# regsimple2addfp_copy.net
KiCad netlist of a schematic drawn in EAGLE
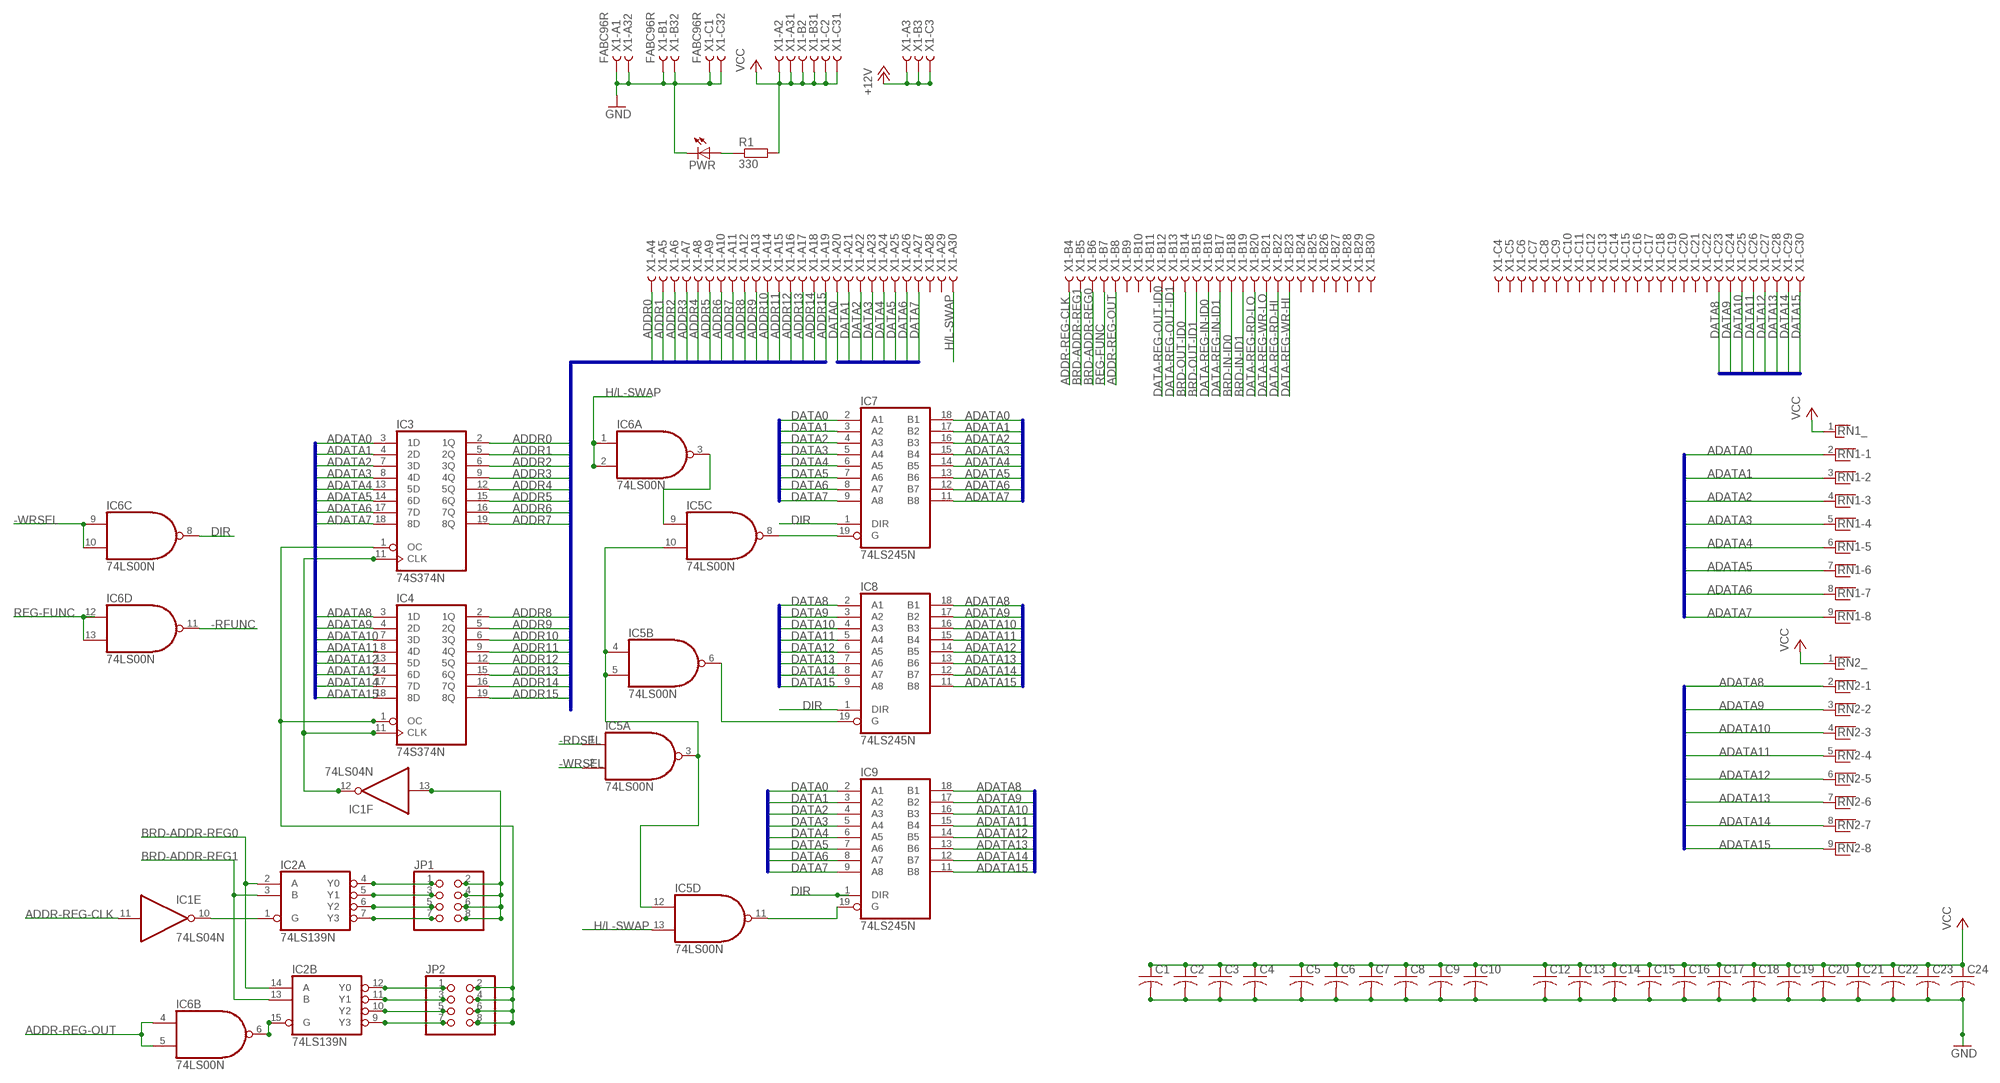
[diagram p0: schematic, sheet 1]
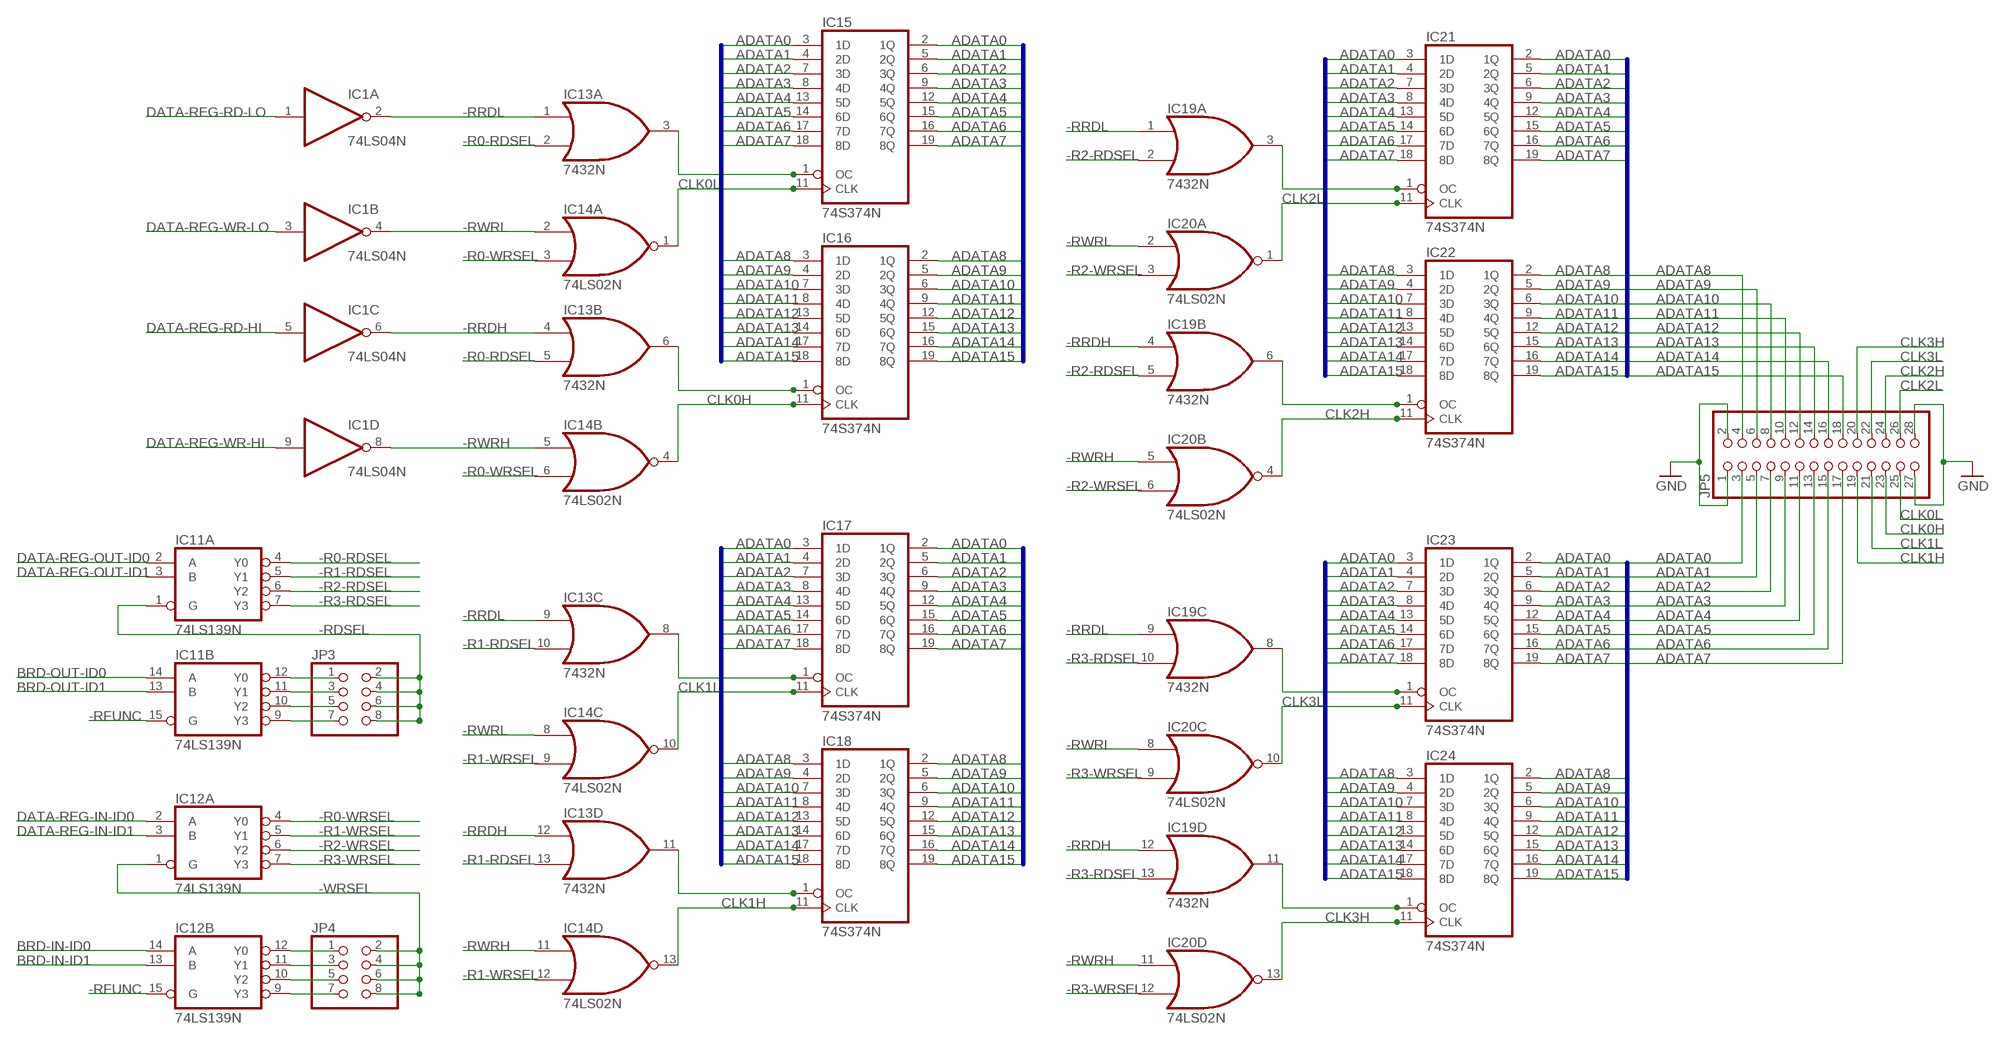
[diagram p1: schematic, sheet 2]

(export (version "E")
  (design (tool "Eeschema 10.0.6"))
  (components
    (comp (ref "C1")
      (value "C-US025-040X050")
      (footprint "eagle-import:C025-040X050")
      (libsource (lib "eagle-import") (part "C-US025-040X050"))
    )
    (comp (ref "C2")
      (value "C-US025-040X050")
      (footprint "eagle-import:C025-040X050")
      (libsource (lib "eagle-import") (part "C-US025-040X050"))
    )
    (comp (ref "C3")
      (value "C-US025-040X050")
      (footprint "eagle-import:C025-040X050")
      (libsource (lib "eagle-import") (part "C-US025-040X050"))
    )
    (comp (ref "C4")
      (value "C-US025-040X050")
      (footprint "eagle-import:C025-040X050")
      (libsource (lib "eagle-import") (part "C-US025-040X050"))
    )
    (comp (ref "C5")
      (value "C-US025-040X050")
      (footprint "eagle-import:C025-040X050")
      (libsource (lib "eagle-import") (part "C-US025-040X050"))
    )
    (comp (ref "C6")
      (value "C-US025-040X050")
      (footprint "eagle-import:C025-040X050")
      (libsource (lib "eagle-import") (part "C-US025-040X050"))
    )
    (comp (ref "C7")
      (value "C-US025-040X050")
      (footprint "eagle-import:C025-040X050")
      (libsource (lib "eagle-import") (part "C-US025-040X050"))
    )
    (comp (ref "C8")
      (value "C-US025-040X050")
      (footprint "eagle-import:C025-040X050")
      (libsource (lib "eagle-import") (part "C-US025-040X050"))
    )
    (comp (ref "C9")
      (value "C-US025-040X050")
      (footprint "eagle-import:C025-040X050")
      (libsource (lib "eagle-import") (part "C-US025-040X050"))
    )
    (comp (ref "C10")
      (value "C-US025-040X050")
      (footprint "eagle-import:C025-040X050")
      (libsource (lib "eagle-import") (part "C-US025-040X050"))
    )
    (comp (ref "C12")
      (value "C-US025-040X050")
      (footprint "eagle-import:C025-040X050")
      (libsource (lib "eagle-import") (part "C-US025-040X050"))
    )
    (comp (ref "C13")
      (value "C-US025-040X050")
      (footprint "eagle-import:C025-040X050")
      (libsource (lib "eagle-import") (part "C-US025-040X050"))
    )
    (comp (ref "C14")
      (value "C-US025-040X050")
      (footprint "eagle-import:C025-040X050")
      (libsource (lib "eagle-import") (part "C-US025-040X050"))
    )
    (comp (ref "C15")
      (value "C-US025-040X050")
      (footprint "eagle-import:C025-040X050")
      (libsource (lib "eagle-import") (part "C-US025-040X050"))
    )
    (comp (ref "C16")
      (value "C-US025-040X050")
      (footprint "eagle-import:C025-040X050")
      (libsource (lib "eagle-import") (part "C-US025-040X050"))
    )
    (comp (ref "C17")
      (value "C-US025-040X050")
      (footprint "eagle-import:C025-040X050")
      (libsource (lib "eagle-import") (part "C-US025-040X050"))
    )
    (comp (ref "C18")
      (value "C-US025-040X050")
      (footprint "eagle-import:C025-040X050")
      (libsource (lib "eagle-import") (part "C-US025-040X050"))
    )
    (comp (ref "C19")
      (value "C-US025-040X050")
      (footprint "eagle-import:C025-040X050")
      (libsource (lib "eagle-import") (part "C-US025-040X050"))
    )
    (comp (ref "C20")
      (value "C-US025-040X050")
      (footprint "eagle-import:C025-040X050")
      (libsource (lib "eagle-import") (part "C-US025-040X050"))
    )
    (comp (ref "C21")
      (value "C-US025-040X050")
      (footprint "eagle-import:C025-040X050")
      (libsource (lib "eagle-import") (part "C-US025-040X050"))
    )
    (comp (ref "C22")
      (value "C-US025-040X050")
      (footprint "eagle-import:C025-040X050")
      (libsource (lib "eagle-import") (part "C-US025-040X050"))
    )
    (comp (ref "C23")
      (value "C-US025-040X050")
      (footprint "eagle-import:C025-040X050")
      (libsource (lib "eagle-import") (part "C-US025-040X050"))
    )
    (comp (ref "C24")
      (value "C-US025-040X050")
      (footprint "eagle-import:C025-040X050")
      (libsource (lib "eagle-import") (part "C-US025-040X050"))
    )
    (comp (ref "IC1")
      (value "74LS04N")
      (footprint "eagle-import:DIL14")
      (libsource (lib "eagle-import") (part "7404NLS"))
    )
    (comp (ref "IC2")
      (value "74LS139N")
      (footprint "eagle-import:DIL16")
      (libsource (lib "eagle-import") (part "74139NLS"))
    )
    (comp (ref "IC3")
      (value "74S374N")
      (footprint "eagle-import:DIL20")
      (libsource (lib "eagle-import") (part "74374NS"))
    )
    (comp (ref "IC4")
      (value "74S374N")
      (footprint "eagle-import:DIL20")
      (libsource (lib "eagle-import") (part "74374NS"))
    )
    (comp (ref "IC5")
      (value "74LS00N")
      (footprint "eagle-import:DIL14")
      (libsource (lib "eagle-import") (part "7400NLS"))
    )
    (comp (ref "IC6")
      (value "74LS00N")
      (footprint "eagle-import:DIL14")
      (libsource (lib "eagle-import") (part "7400NLS"))
    )
    (comp (ref "IC7")
      (value "74LS245N")
      (footprint "eagle-import:DIL20")
      (libsource (lib "eagle-import") (part "74245NLS"))
    )
    (comp (ref "IC8")
      (value "74LS245N")
      (footprint "eagle-import:DIL20")
      (libsource (lib "eagle-import") (part "74245NLS"))
    )
    (comp (ref "IC9")
      (value "74LS245N")
      (footprint "eagle-import:DIL20")
      (libsource (lib "eagle-import") (part "74245NLS"))
    )
    (comp (ref "JP1")
      (value "PINHD-2X4")
      (footprint "eagle-import:2X04")
      (libsource (lib "eagle-import") (part "PINHD-2X4"))
    )
    (comp (ref "JP2")
      (value "PINHD-2X4")
      (footprint "eagle-import:2X04")
      (libsource (lib "eagle-import") (part "PINHD-2X4"))
    )
    (comp (ref "PWR")
      (value "LED5MM")
      (footprint "eagle-import:LED5MM")
      (libsource (lib "eagle-import") (part "LED5MM"))
    )
    (comp (ref "R1")
      (value "330")
      (footprint "eagle-import:0207_10")
      (libsource (lib "eagle-import") (part "R0207/10"))
    )
    (comp (ref "RN1")
      (value "RNX8")
      (footprint "eagle-import:RN-9")
      (libsource (lib "eagle-import") (part "RNX8"))
    )
    (comp (ref "RN2")
      (value "RNX8")
      (footprint "eagle-import:RN-9")
      (libsource (lib "eagle-import") (part "RNX8"))
    )
    (comp (ref "X1")
      (value "FABC96R")
      (footprint "eagle-import:FABC96R")
      (libsource (lib "eagle-import") (part "FABC96R"))
    )
    (comp (ref "IC11")
      (value "74LS139N")
      (footprint "eagle-import:DIL16")
      (libsource (lib "eagle-import") (part "74139NLS"))
    )
    (comp (ref "IC12")
      (value "74LS139N")
      (footprint "eagle-import:DIL16")
      (libsource (lib "eagle-import") (part "74139NLS"))
    )
    (comp (ref "IC13")
      (value "7432N")
      (footprint "eagle-import:DIL14")
      (libsource (lib "eagle-import") (part "7432N"))
    )
    (comp (ref "IC14")
      (value "74LS02N")
      (footprint "eagle-import:DIL14")
      (libsource (lib "eagle-import") (part "7402NLS"))
    )
    (comp (ref "IC15")
      (value "74S374N")
      (footprint "eagle-import:DIL20")
      (libsource (lib "eagle-import") (part "74374NS"))
    )
    (comp (ref "IC16")
      (value "74S374N")
      (footprint "eagle-import:DIL20")
      (libsource (lib "eagle-import") (part "74374NS"))
    )
    (comp (ref "IC17")
      (value "74S374N")
      (footprint "eagle-import:DIL20")
      (libsource (lib "eagle-import") (part "74374NS"))
    )
    (comp (ref "IC18")
      (value "74S374N")
      (footprint "eagle-import:DIL20")
      (libsource (lib "eagle-import") (part "74374NS"))
    )
    (comp (ref "IC19")
      (value "7432N")
      (footprint "eagle-import:DIL14")
      (libsource (lib "eagle-import") (part "7432N"))
    )
    (comp (ref "IC20")
      (value "74LS02N")
      (footprint "eagle-import:DIL14")
      (libsource (lib "eagle-import") (part "7402NLS"))
    )
    (comp (ref "IC21")
      (value "74S374N")
      (footprint "eagle-import:DIL20")
      (libsource (lib "eagle-import") (part "74374NS"))
    )
    (comp (ref "IC22")
      (value "74S374N")
      (footprint "eagle-import:DIL20")
      (libsource (lib "eagle-import") (part "74374NS"))
    )
    (comp (ref "IC23")
      (value "74S374N")
      (footprint "eagle-import:DIL20")
      (libsource (lib "eagle-import") (part "74374NS"))
    )
    (comp (ref "IC24")
      (value "74S374N")
      (footprint "eagle-import:DIL20")
      (libsource (lib "eagle-import") (part "74374NS"))
    )
    (comp (ref "JP3")
      (value "PINHD-2X4")
      (footprint "eagle-import:2X04")
      (libsource (lib "eagle-import") (part "PINHD-2X4"))
    )
    (comp (ref "JP4")
      (value "PINHD-2X4")
      (footprint "eagle-import:2X04")
      (libsource (lib "eagle-import") (part "PINHD-2X4"))
    )
    (comp (ref "JP5")
      (value "PINHD-2X14")
      (footprint "eagle-import:2X14")
      (libsource (lib "eagle-import") (part "PINHD-2X14"))
    )
  )
  (nets
    (net (code "1") (name "+12V") (class "Default")
      (node (ref "X1") (pin "A3") (pinfunction "B_A3") (pintype "passive"))
      (node (ref "X1") (pin "B3") (pinfunction "B_B3") (pintype "passive"))
      (node (ref "X1") (pin "C3") (pinfunction "B_C3") (pintype "passive"))
    )
    (net (code "2") (name "-R0-RDSEL") (class "Default")
      (node (ref "IC11") (pin "4") (pinfunction "Y0_4") (pintype "output"))
      (node (ref "IC13") (pin "2") (pinfunction "I1_2") (pintype "input"))
      (node (ref "IC13") (pin "5") (pinfunction "I1_5") (pintype "input"))
    )
    (net (code "3") (name "-R0-WRSEL") (class "Default")
      (node (ref "IC12") (pin "4") (pinfunction "Y0_4") (pintype "output"))
      (node (ref "IC14") (pin "3") (pinfunction "I1_3") (pintype "input"))
      (node (ref "IC14") (pin "6") (pinfunction "I1_6") (pintype "input"))
    )
    (net (code "4") (name "-R1-RDSEL") (class "Default")
      (node (ref "IC11") (pin "5") (pinfunction "Y1_5") (pintype "output"))
      (node (ref "IC13") (pin "10") (pinfunction "I1_10") (pintype "input"))
      (node (ref "IC13") (pin "13") (pinfunction "I1_13") (pintype "input"))
    )
    (net (code "5") (name "-R1-WRSEL") (class "Default")
      (node (ref "IC12") (pin "5") (pinfunction "Y1_5") (pintype "output"))
      (node (ref "IC14") (pin "12") (pinfunction "I1_12") (pintype "input"))
      (node (ref "IC14") (pin "9") (pinfunction "I1_9") (pintype "input"))
    )
    (net (code "6") (name "-R2-RDSEL") (class "Default")
      (node (ref "IC11") (pin "6") (pinfunction "Y2_6") (pintype "output"))
      (node (ref "IC19") (pin "2") (pinfunction "I1_2") (pintype "input"))
      (node (ref "IC19") (pin "5") (pinfunction "I1_5") (pintype "input"))
    )
    (net (code "7") (name "-R2-WRSEL") (class "Default")
      (node (ref "IC12") (pin "6") (pinfunction "Y2_6") (pintype "output"))
      (node (ref "IC20") (pin "3") (pinfunction "I1_3") (pintype "input"))
      (node (ref "IC20") (pin "6") (pinfunction "I1_6") (pintype "input"))
    )
    (net (code "8") (name "-R3-RDSEL") (class "Default")
      (node (ref "IC11") (pin "7") (pinfunction "Y3_7") (pintype "output"))
      (node (ref "IC19") (pin "10") (pinfunction "I1_10") (pintype "input"))
      (node (ref "IC19") (pin "13") (pinfunction "I1_13") (pintype "input"))
    )
    (net (code "9") (name "-R3-WRSEL") (class "Default")
      (node (ref "IC12") (pin "7") (pinfunction "Y3_7") (pintype "output"))
      (node (ref "IC20") (pin "12") (pinfunction "I1_12") (pintype "input"))
      (node (ref "IC20") (pin "9") (pinfunction "I1_9") (pintype "input"))
    )
    (net (code "10") (name "-RDSEL") (class "Default")
      (node (ref "IC11") (pin "1") (pinfunction "G_1") (pintype "input"))
      (node (ref "IC5") (pin "1") (pinfunction "I0_1") (pintype "input"))
      (node (ref "JP3") (pin "2") (pinfunction "2_2") (pintype "passive"))
      (node (ref "JP3") (pin "4") (pinfunction "4_4") (pintype "passive"))
      (node (ref "JP3") (pin "6") (pinfunction "6_6") (pintype "passive"))
      (node (ref "JP3") (pin "8") (pinfunction "8_8") (pintype "passive"))
    )
    (net (code "11") (name "-RFUNC") (class "Default")
      (node (ref "IC11") (pin "15") (pinfunction "G_15") (pintype "input"))
      (node (ref "IC12") (pin "15") (pinfunction "G_15") (pintype "input"))
      (node (ref "IC6") (pin "11") (pinfunction "O_11") (pintype "output"))
    )
    (net (code "12") (name "-RRDH") (class "Default")
      (node (ref "IC1") (pin "6") (pinfunction "O_6") (pintype "output"))
      (node (ref "IC13") (pin "12") (pinfunction "I0_12") (pintype "input"))
      (node (ref "IC13") (pin "4") (pinfunction "I0_4") (pintype "input"))
      (node (ref "IC19") (pin "12") (pinfunction "I0_12") (pintype "input"))
      (node (ref "IC19") (pin "4") (pinfunction "I0_4") (pintype "input"))
    )
    (net (code "13") (name "-RRDL") (class "Default")
      (node (ref "IC1") (pin "2") (pinfunction "O_2") (pintype "output"))
      (node (ref "IC13") (pin "1") (pinfunction "I0_1") (pintype "input"))
      (node (ref "IC13") (pin "9") (pinfunction "I0_9") (pintype "input"))
      (node (ref "IC19") (pin "1") (pinfunction "I0_1") (pintype "input"))
      (node (ref "IC19") (pin "9") (pinfunction "I0_9") (pintype "input"))
    )
    (net (code "14") (name "-RWRH") (class "Default")
      (node (ref "IC1") (pin "8") (pinfunction "O_8") (pintype "output"))
      (node (ref "IC14") (pin "11") (pinfunction "I0_11") (pintype "input"))
      (node (ref "IC14") (pin "5") (pinfunction "I0_5") (pintype "input"))
      (node (ref "IC20") (pin "11") (pinfunction "I0_11") (pintype "input"))
      (node (ref "IC20") (pin "5") (pinfunction "I0_5") (pintype "input"))
    )
    (net (code "15") (name "-RWRL") (class "Default")
      (node (ref "IC1") (pin "4") (pinfunction "O_4") (pintype "output"))
      (node (ref "IC14") (pin "2") (pinfunction "I0_2") (pintype "input"))
      (node (ref "IC14") (pin "8") (pinfunction "I0_8") (pintype "input"))
      (node (ref "IC20") (pin "2") (pinfunction "I0_2") (pintype "input"))
      (node (ref "IC20") (pin "8") (pinfunction "I0_8") (pintype "input"))
    )
    (net (code "16") (name "-WRSEL") (class "Default")
      (node (ref "IC12") (pin "1") (pinfunction "G_1") (pintype "input"))
      (node (ref "IC5") (pin "2") (pinfunction "I1_2") (pintype "input"))
      (node (ref "IC6") (pin "10") (pinfunction "I1_10") (pintype "input"))
      (node (ref "IC6") (pin "9") (pinfunction "I0_9") (pintype "input"))
      (node (ref "JP4") (pin "2") (pinfunction "2_2") (pintype "passive"))
      (node (ref "JP4") (pin "4") (pinfunction "4_4") (pintype "passive"))
      (node (ref "JP4") (pin "6") (pinfunction "6_6") (pintype "passive"))
      (node (ref "JP4") (pin "8") (pinfunction "8_8") (pintype "passive"))
    )
    (net (code "17") (name "ADATA0") (class "Default")
      (node (ref "IC15") (pin "2") (pinfunction "1Q_2") (pintype "tri_state"))
      (node (ref "IC15") (pin "3") (pinfunction "1D_3") (pintype "input"))
      (node (ref "IC17") (pin "2") (pinfunction "1Q_2") (pintype "tri_state"))
      (node (ref "IC17") (pin "3") (pinfunction "1D_3") (pintype "input"))
      (node (ref "IC21") (pin "2") (pinfunction "1Q_2") (pintype "tri_state"))
      (node (ref "IC21") (pin "3") (pinfunction "1D_3") (pintype "input"))
      (node (ref "IC23") (pin "2") (pinfunction "1Q_2") (pintype "tri_state"))
      (node (ref "IC23") (pin "3") (pinfunction "1D_3") (pintype "input"))
      (node (ref "IC3") (pin "3") (pinfunction "1D_3") (pintype "input"))
      (node (ref "IC7") (pin "18") (pinfunction "B1_18") (pintype "bidirectional"))
      (node (ref "JP5") (pin "3") (pinfunction "3_3") (pintype "passive"))
      (node (ref "RN1") (pin "2") (pinfunction "1_2") (pintype "passive"))
    )
    (net (code "18") (name "ADATA1") (class "Default")
      (node (ref "IC15") (pin "4") (pinfunction "2D_4") (pintype "input"))
      (node (ref "IC15") (pin "5") (pinfunction "2Q_5") (pintype "tri_state"))
      (node (ref "IC17") (pin "4") (pinfunction "2D_4") (pintype "input"))
      (node (ref "IC17") (pin "5") (pinfunction "2Q_5") (pintype "tri_state"))
      (node (ref "IC21") (pin "4") (pinfunction "2D_4") (pintype "input"))
      (node (ref "IC21") (pin "5") (pinfunction "2Q_5") (pintype "tri_state"))
      (node (ref "IC23") (pin "4") (pinfunction "2D_4") (pintype "input"))
      (node (ref "IC23") (pin "5") (pinfunction "2Q_5") (pintype "tri_state"))
      (node (ref "IC3") (pin "4") (pinfunction "2D_4") (pintype "input"))
      (node (ref "IC7") (pin "17") (pinfunction "B2_17") (pintype "bidirectional"))
      (node (ref "JP5") (pin "5") (pinfunction "5_5") (pintype "passive"))
      (node (ref "RN1") (pin "3") (pinfunction "1_3") (pintype "passive"))
    )
    (net (code "19") (name "ADATA2") (class "Default")
      (node (ref "IC15") (pin "6") (pinfunction "3Q_6") (pintype "tri_state"))
      (node (ref "IC15") (pin "7") (pinfunction "3D_7") (pintype "input"))
      (node (ref "IC17") (pin "6") (pinfunction "3Q_6") (pintype "tri_state"))
      (node (ref "IC17") (pin "7") (pinfunction "3D_7") (pintype "input"))
      (node (ref "IC21") (pin "6") (pinfunction "3Q_6") (pintype "tri_state"))
      (node (ref "IC21") (pin "7") (pinfunction "3D_7") (pintype "input"))
      (node (ref "IC23") (pin "6") (pinfunction "3Q_6") (pintype "tri_state"))
      (node (ref "IC23") (pin "7") (pinfunction "3D_7") (pintype "input"))
      (node (ref "IC3") (pin "7") (pinfunction "3D_7") (pintype "input"))
      (node (ref "IC7") (pin "16") (pinfunction "B3_16") (pintype "bidirectional"))
      (node (ref "JP5") (pin "7") (pinfunction "7_7") (pintype "passive"))
      (node (ref "RN1") (pin "4") (pinfunction "1_4") (pintype "passive"))
    )
    (net (code "20") (name "ADATA3") (class "Default")
      (node (ref "IC15") (pin "8") (pinfunction "4D_8") (pintype "input"))
      (node (ref "IC15") (pin "9") (pinfunction "4Q_9") (pintype "tri_state"))
      (node (ref "IC17") (pin "8") (pinfunction "4D_8") (pintype "input"))
      (node (ref "IC17") (pin "9") (pinfunction "4Q_9") (pintype "tri_state"))
      (node (ref "IC21") (pin "8") (pinfunction "4D_8") (pintype "input"))
      (node (ref "IC21") (pin "9") (pinfunction "4Q_9") (pintype "tri_state"))
      (node (ref "IC23") (pin "8") (pinfunction "4D_8") (pintype "input"))
      (node (ref "IC23") (pin "9") (pinfunction "4Q_9") (pintype "tri_state"))
      (node (ref "IC3") (pin "8") (pinfunction "4D_8") (pintype "input"))
      (node (ref "IC7") (pin "15") (pinfunction "B4_15") (pintype "bidirectional"))
      (node (ref "JP5") (pin "9") (pinfunction "9_9") (pintype "passive"))
      (node (ref "RN1") (pin "5") (pinfunction "1_5") (pintype "passive"))
    )
    (net (code "21") (name "ADATA4") (class "Default")
      (node (ref "IC15") (pin "12") (pinfunction "5Q_12") (pintype "tri_state"))
      (node (ref "IC15") (pin "13") (pinfunction "5D_13") (pintype "input"))
      (node (ref "IC17") (pin "12") (pinfunction "5Q_12") (pintype "tri_state"))
      (node (ref "IC17") (pin "13") (pinfunction "5D_13") (pintype "input"))
      (node (ref "IC21") (pin "12") (pinfunction "5Q_12") (pintype "tri_state"))
      (node (ref "IC21") (pin "13") (pinfunction "5D_13") (pintype "input"))
      (node (ref "IC23") (pin "12") (pinfunction "5Q_12") (pintype "tri_state"))
      (node (ref "IC23") (pin "13") (pinfunction "5D_13") (pintype "input"))
      (node (ref "IC3") (pin "13") (pinfunction "5D_13") (pintype "input"))
      (node (ref "IC7") (pin "14") (pinfunction "B5_14") (pintype "bidirectional"))
      (node (ref "JP5") (pin "11") (pinfunction "11_11") (pintype "passive"))
      (node (ref "RN1") (pin "6") (pinfunction "1_6") (pintype "passive"))
    )
    (net (code "22") (name "ADATA5") (class "Default")
      (node (ref "IC15") (pin "14") (pinfunction "6D_14") (pintype "input"))
      (node (ref "IC15") (pin "15") (pinfunction "6Q_15") (pintype "tri_state"))
      (node (ref "IC17") (pin "14") (pinfunction "6D_14") (pintype "input"))
      (node (ref "IC17") (pin "15") (pinfunction "6Q_15") (pintype "tri_state"))
      (node (ref "IC21") (pin "14") (pinfunction "6D_14") (pintype "input"))
      (node (ref "IC21") (pin "15") (pinfunction "6Q_15") (pintype "tri_state"))
      (node (ref "IC23") (pin "14") (pinfunction "6D_14") (pintype "input"))
      (node (ref "IC23") (pin "15") (pinfunction "6Q_15") (pintype "tri_state"))
      (node (ref "IC3") (pin "14") (pinfunction "6D_14") (pintype "input"))
      (node (ref "IC7") (pin "13") (pinfunction "B6_13") (pintype "bidirectional"))
      (node (ref "JP5") (pin "13") (pinfunction "13_13") (pintype "passive"))
      (node (ref "RN1") (pin "7") (pinfunction "1_7") (pintype "passive"))
    )
    (net (code "23") (name "ADATA6") (class "Default")
      (node (ref "IC15") (pin "16") (pinfunction "7Q_16") (pintype "tri_state"))
      (node (ref "IC15") (pin "17") (pinfunction "7D_17") (pintype "input"))
      (node (ref "IC17") (pin "16") (pinfunction "7Q_16") (pintype "tri_state"))
      (node (ref "IC17") (pin "17") (pinfunction "7D_17") (pintype "input"))
      (node (ref "IC21") (pin "16") (pinfunction "7Q_16") (pintype "tri_state"))
      (node (ref "IC21") (pin "17") (pinfunction "7D_17") (pintype "input"))
      (node (ref "IC23") (pin "16") (pinfunction "7Q_16") (pintype "tri_state"))
      (node (ref "IC23") (pin "17") (pinfunction "7D_17") (pintype "input"))
      (node (ref "IC3") (pin "17") (pinfunction "7D_17") (pintype "input"))
      (node (ref "IC7") (pin "12") (pinfunction "B7_12") (pintype "bidirectional"))
      (node (ref "JP5") (pin "15") (pinfunction "15_15") (pintype "passive"))
      (node (ref "RN1") (pin "8") (pinfunction "1_8") (pintype "passive"))
    )
    (net (code "24") (name "ADATA7") (class "Default")
      (node (ref "IC15") (pin "18") (pinfunction "8D_18") (pintype "input"))
      (node (ref "IC15") (pin "19") (pinfunction "8Q_19") (pintype "tri_state"))
      (node (ref "IC17") (pin "18") (pinfunction "8D_18") (pintype "input"))
      (node (ref "IC17") (pin "19") (pinfunction "8Q_19") (pintype "tri_state"))
      (node (ref "IC21") (pin "18") (pinfunction "8D_18") (pintype "input"))
      (node (ref "IC21") (pin "19") (pinfunction "8Q_19") (pintype "tri_state"))
      (node (ref "IC23") (pin "18") (pinfunction "8D_18") (pintype "input"))
      (node (ref "IC23") (pin "19") (pinfunction "8Q_19") (pintype "tri_state"))
      (node (ref "IC3") (pin "18") (pinfunction "8D_18") (pintype "input"))
      (node (ref "IC7") (pin "11") (pinfunction "B8_11") (pintype "bidirectional"))
      (node (ref "JP5") (pin "17") (pinfunction "17_17") (pintype "passive"))
      (node (ref "RN1") (pin "9") (pinfunction "1_9") (pintype "passive"))
    )
    (net (code "25") (name "ADATA8") (class "Default")
      (node (ref "IC16") (pin "2") (pinfunction "1Q_2") (pintype "tri_state"))
      (node (ref "IC16") (pin "3") (pinfunction "1D_3") (pintype "input"))
      (node (ref "IC18") (pin "2") (pinfunction "1Q_2") (pintype "tri_state"))
      (node (ref "IC18") (pin "3") (pinfunction "1D_3") (pintype "input"))
      (node (ref "IC22") (pin "2") (pinfunction "1Q_2") (pintype "tri_state"))
      (node (ref "IC22") (pin "3") (pinfunction "1D_3") (pintype "input"))
      (node (ref "IC24") (pin "2") (pinfunction "1Q_2") (pintype "tri_state"))
      (node (ref "IC24") (pin "3") (pinfunction "1D_3") (pintype "input"))
      (node (ref "IC4") (pin "3") (pinfunction "1D_3") (pintype "input"))
      (node (ref "IC8") (pin "18") (pinfunction "B1_18") (pintype "bidirectional"))
      (node (ref "IC9") (pin "18") (pinfunction "B1_18") (pintype "bidirectional"))
      (node (ref "JP5") (pin "4") (pinfunction "4_4") (pintype "passive"))
      (node (ref "RN2") (pin "2") (pinfunction "1_2") (pintype "passive"))
    )
    (net (code "26") (name "ADATA9") (class "Default")
      (node (ref "IC16") (pin "4") (pinfunction "2D_4") (pintype "input"))
      (node (ref "IC16") (pin "5") (pinfunction "2Q_5") (pintype "tri_state"))
      (node (ref "IC18") (pin "4") (pinfunction "2D_4") (pintype "input"))
      (node (ref "IC18") (pin "5") (pinfunction "2Q_5") (pintype "tri_state"))
      (node (ref "IC22") (pin "4") (pinfunction "2D_4") (pintype "input"))
      (node (ref "IC22") (pin "5") (pinfunction "2Q_5") (pintype "tri_state"))
      (node (ref "IC24") (pin "4") (pinfunction "2D_4") (pintype "input"))
      (node (ref "IC24") (pin "5") (pinfunction "2Q_5") (pintype "tri_state"))
      (node (ref "IC4") (pin "4") (pinfunction "2D_4") (pintype "input"))
      (node (ref "IC8") (pin "17") (pinfunction "B2_17") (pintype "bidirectional"))
      (node (ref "IC9") (pin "17") (pinfunction "B2_17") (pintype "bidirectional"))
      (node (ref "JP5") (pin "6") (pinfunction "6_6") (pintype "passive"))
      (node (ref "RN2") (pin "3") (pinfunction "1_3") (pintype "passive"))
    )
    (net (code "27") (name "ADATA10") (class "Default")
      (node (ref "IC16") (pin "6") (pinfunction "3Q_6") (pintype "tri_state"))
      (node (ref "IC16") (pin "7") (pinfunction "3D_7") (pintype "input"))
      (node (ref "IC18") (pin "6") (pinfunction "3Q_6") (pintype "tri_state"))
      (node (ref "IC18") (pin "7") (pinfunction "3D_7") (pintype "input"))
      (node (ref "IC22") (pin "6") (pinfunction "3Q_6") (pintype "tri_state"))
      (node (ref "IC22") (pin "7") (pinfunction "3D_7") (pintype "input"))
      (node (ref "IC24") (pin "6") (pinfunction "3Q_6") (pintype "tri_state"))
      (node (ref "IC24") (pin "7") (pinfunction "3D_7") (pintype "input"))
      (node (ref "IC4") (pin "7") (pinfunction "3D_7") (pintype "input"))
      (node (ref "IC8") (pin "16") (pinfunction "B3_16") (pintype "bidirectional"))
      (node (ref "IC9") (pin "16") (pinfunction "B3_16") (pintype "bidirectional"))
      (node (ref "JP5") (pin "8") (pinfunction "8_8") (pintype "passive"))
      (node (ref "RN2") (pin "4") (pinfunction "1_4") (pintype "passive"))
    )
    (net (code "28") (name "ADATA11") (class "Default")
      (node (ref "IC16") (pin "8") (pinfunction "4D_8") (pintype "input"))
      (node (ref "IC16") (pin "9") (pinfunction "4Q_9") (pintype "tri_state"))
      (node (ref "IC18") (pin "8") (pinfunction "4D_8") (pintype "input"))
      (node (ref "IC18") (pin "9") (pinfunction "4Q_9") (pintype "tri_state"))
      (node (ref "IC22") (pin "8") (pinfunction "4D_8") (pintype "input"))
      (node (ref "IC22") (pin "9") (pinfunction "4Q_9") (pintype "tri_state"))
      (node (ref "IC24") (pin "8") (pinfunction "4D_8") (pintype "input"))
      (node (ref "IC24") (pin "9") (pinfunction "4Q_9") (pintype "tri_state"))
      (node (ref "IC4") (pin "8") (pinfunction "4D_8") (pintype "input"))
      (node (ref "IC8") (pin "15") (pinfunction "B4_15") (pintype "bidirectional"))
      (node (ref "IC9") (pin "15") (pinfunction "B4_15") (pintype "bidirectional"))
      (node (ref "JP5") (pin "10") (pinfunction "10_10") (pintype "passive"))
      (node (ref "RN2") (pin "5") (pinfunction "1_5") (pintype "passive"))
    )
    (net (code "29") (name "ADATA12") (class "Default")
      (node (ref "IC16") (pin "12") (pinfunction "5Q_12") (pintype "tri_state"))
      (node (ref "IC16") (pin "13") (pinfunction "5D_13") (pintype "input"))
      (node (ref "IC18") (pin "12") (pinfunction "5Q_12") (pintype "tri_state"))
      (node (ref "IC18") (pin "13") (pinfunction "5D_13") (pintype "input"))
      (node (ref "IC22") (pin "12") (pinfunction "5Q_12") (pintype "tri_state"))
      (node (ref "IC22") (pin "13") (pinfunction "5D_13") (pintype "input"))
      (node (ref "IC24") (pin "12") (pinfunction "5Q_12") (pintype "tri_state"))
      (node (ref "IC24") (pin "13") (pinfunction "5D_13") (pintype "input"))
      (node (ref "IC4") (pin "13") (pinfunction "5D_13") (pintype "input"))
      (node (ref "IC8") (pin "14") (pinfunction "B5_14") (pintype "bidirectional"))
      (node (ref "IC9") (pin "14") (pinfunction "B5_14") (pintype "bidirectional"))
      (node (ref "JP5") (pin "12") (pinfunction "12_12") (pintype "passive"))
      (node (ref "RN2") (pin "6") (pinfunction "1_6") (pintype "passive"))
    )
    (net (code "30") (name "ADATA13") (class "Default")
      (node (ref "IC16") (pin "14") (pinfunction "6D_14") (pintype "input"))
      (node (ref "IC16") (pin "15") (pinfunction "6Q_15") (pintype "tri_state"))
      (node (ref "IC18") (pin "14") (pinfunction "6D_14") (pintype "input"))
      (node (ref "IC18") (pin "15") (pinfunction "6Q_15") (pintype "tri_state"))
      (node (ref "IC22") (pin "14") (pinfunction "6D_14") (pintype "input"))
      (node (ref "IC22") (pin "15") (pinfunction "6Q_15") (pintype "tri_state"))
      (node (ref "IC24") (pin "14") (pinfunction "6D_14") (pintype "input"))
      (node (ref "IC24") (pin "15") (pinfunction "6Q_15") (pintype "tri_state"))
      (node (ref "IC4") (pin "14") (pinfunction "6D_14") (pintype "input"))
      (node (ref "IC8") (pin "13") (pinfunction "B6_13") (pintype "bidirectional"))
      (node (ref "IC9") (pin "13") (pinfunction "B6_13") (pintype "bidirectional"))
      (node (ref "JP5") (pin "14") (pinfunction "14_14") (pintype "passive"))
      (node (ref "RN2") (pin "7") (pinfunction "1_7") (pintype "passive"))
    )
    (net (code "31") (name "ADATA14") (class "Default")
      (node (ref "IC16") (pin "16") (pinfunction "7Q_16") (pintype "tri_state"))
      (node (ref "IC16") (pin "17") (pinfunction "7D_17") (pintype "input"))
      (node (ref "IC18") (pin "16") (pinfunction "7Q_16") (pintype "tri_state"))
      (node (ref "IC18") (pin "17") (pinfunction "7D_17") (pintype "input"))
      (node (ref "IC22") (pin "16") (pinfunction "7Q_16") (pintype "tri_state"))
      (node (ref "IC22") (pin "17") (pinfunction "7D_17") (pintype "input"))
      (node (ref "IC24") (pin "16") (pinfunction "7Q_16") (pintype "tri_state"))
      (node (ref "IC24") (pin "17") (pinfunction "7D_17") (pintype "input"))
      (node (ref "IC4") (pin "17") (pinfunction "7D_17") (pintype "input"))
      (node (ref "IC8") (pin "12") (pinfunction "B7_12") (pintype "bidirectional"))
      (node (ref "IC9") (pin "12") (pinfunction "B7_12") (pintype "bidirectional"))
      (node (ref "JP5") (pin "16") (pinfunction "16_16") (pintype "passive"))
      (node (ref "RN2") (pin "8") (pinfunction "1_8") (pintype "passive"))
    )
    (net (code "32") (name "ADATA15") (class "Default")
      (node (ref "IC16") (pin "18") (pinfunction "8D_18") (pintype "input"))
      (node (ref "IC16") (pin "19") (pinfunction "8Q_19") (pintype "tri_state"))
      (node (ref "IC18") (pin "18") (pinfunction "8D_18") (pintype "input"))
      (node (ref "IC18") (pin "19") (pinfunction "8Q_19") (pintype "tri_state"))
      (node (ref "IC22") (pin "18") (pinfunction "8D_18") (pintype "input"))
      (node (ref "IC22") (pin "19") (pinfunction "8Q_19") (pintype "tri_state"))
      (node (ref "IC24") (pin "18") (pinfunction "8D_18") (pintype "input"))
      (node (ref "IC24") (pin "19") (pinfunction "8Q_19") (pintype "tri_state"))
      (node (ref "IC4") (pin "18") (pinfunction "8D_18") (pintype "input"))
      (node (ref "IC8") (pin "11") (pinfunction "B8_11") (pintype "bidirectional"))
      (node (ref "IC9") (pin "11") (pinfunction "B8_11") (pintype "bidirectional"))
      (node (ref "JP5") (pin "18") (pinfunction "18_18") (pintype "passive"))
      (node (ref "RN2") (pin "9") (pinfunction "1_9") (pintype "passive"))
    )
    (net (code "33") (name "ADDR-REG-CLK") (class "Default")
      (node (ref "IC1") (pin "11") (pinfunction "I_11") (pintype "input"))
      (node (ref "X1") (pin "B4") (pinfunction "B_B4") (pintype "passive"))
    )
    (net (code "34") (name "ADDR-REG-OUT") (class "Default")
      (node (ref "IC6") (pin "4") (pinfunction "I0_4") (pintype "input"))
      (node (ref "IC6") (pin "5") (pinfunction "I1_5") (pintype "input"))
      (node (ref "X1") (pin "B8") (pinfunction "B_B8") (pintype "passive"))
    )
    (net (code "35") (name "ADDR0") (class "Default")
      (node (ref "IC3") (pin "2") (pinfunction "1Q_2") (pintype "tri_state"))
      (node (ref "X1") (pin "A4") (pinfunction "B_A4") (pintype "passive"))
    )
    (net (code "36") (name "ADDR1") (class "Default")
      (node (ref "IC3") (pin "5") (pinfunction "2Q_5") (pintype "tri_state"))
      (node (ref "X1") (pin "A5") (pinfunction "B_A5") (pintype "passive"))
    )
    (net (code "37") (name "ADDR2") (class "Default")
      (node (ref "IC3") (pin "6") (pinfunction "3Q_6") (pintype "tri_state"))
      (node (ref "X1") (pin "A6") (pinfunction "B_A6") (pintype "passive"))
    )
    (net (code "38") (name "ADDR3") (class "Default")
      (node (ref "IC3") (pin "9") (pinfunction "4Q_9") (pintype "tri_state"))
      (node (ref "X1") (pin "A7") (pinfunction "B_A7") (pintype "passive"))
    )
    (net (code "39") (name "ADDR4") (class "Default")
      (node (ref "IC3") (pin "12") (pinfunction "5Q_12") (pintype "tri_state"))
      (node (ref "X1") (pin "A8") (pinfunction "B_A8") (pintype "passive"))
    )
    (net (code "40") (name "ADDR5") (class "Default")
      (node (ref "IC3") (pin "15") (pinfunction "6Q_15") (pintype "tri_state"))
      (node (ref "X1") (pin "A9") (pinfunction "B_A9") (pintype "passive"))
    )
    (net (code "41") (name "ADDR6") (class "Default")
      (node (ref "IC3") (pin "16") (pinfunction "7Q_16") (pintype "tri_state"))
      (node (ref "X1") (pin "A10") (pinfunction "B_A10") (pintype "passive"))
    )
    (net (code "42") (name "ADDR7") (class "Default")
      (node (ref "IC3") (pin "19") (pinfunction "8Q_19") (pintype "tri_state"))
      (node (ref "X1") (pin "A11") (pinfunction "B_A11") (pintype "passive"))
    )
    (net (code "43") (name "ADDR8") (class "Default")
      (node (ref "IC4") (pin "2") (pinfunction "1Q_2") (pintype "tri_state"))
      (node (ref "X1") (pin "A12") (pinfunction "B_A12") (pintype "passive"))
    )
    (net (code "44") (name "ADDR9") (class "Default")
      (node (ref "IC4") (pin "5") (pinfunction "2Q_5") (pintype "tri_state"))
      (node (ref "X1") (pin "A13") (pinfunction "B_A13") (pintype "passive"))
    )
    (net (code "45") (name "ADDR10") (class "Default")
      (node (ref "IC4") (pin "6") (pinfunction "3Q_6") (pintype "tri_state"))
      (node (ref "X1") (pin "A14") (pinfunction "B_A14") (pintype "passive"))
    )
    (net (code "46") (name "ADDR11") (class "Default")
      (node (ref "IC4") (pin "9") (pinfunction "4Q_9") (pintype "tri_state"))
      (node (ref "X1") (pin "A15") (pinfunction "B_A15") (pintype "passive"))
    )
    (net (code "47") (name "ADDR12") (class "Default")
      (node (ref "IC4") (pin "12") (pinfunction "5Q_12") (pintype "tri_state"))
      (node (ref "X1") (pin "A16") (pinfunction "B_A16") (pintype "passive"))
    )
    (net (code "48") (name "ADDR13") (class "Default")
      (node (ref "IC4") (pin "15") (pinfunction "6Q_15") (pintype "tri_state"))
      (node (ref "X1") (pin "A17") (pinfunction "B_A17") (pintype "passive"))
    )
    (net (code "49") (name "ADDR14") (class "Default")
      (node (ref "IC4") (pin "16") (pinfunction "7Q_16") (pintype "tri_state"))
      (node (ref "X1") (pin "A18") (pinfunction "B_A18") (pintype "passive"))
    )
    (net (code "50") (name "ADDR15") (class "Default")
      (node (ref "IC4") (pin "19") (pinfunction "8Q_19") (pintype "tri_state"))
      (node (ref "X1") (pin "A19") (pinfunction "B_A19") (pintype "passive"))
    )
    (net (code "51") (name "BRD-ADDR-REG0") (class "Default")
      (node (ref "IC2") (pin "14") (pinfunction "A_14") (pintype "input"))
      (node (ref "IC2") (pin "2") (pinfunction "A_2") (pintype "input"))
      (node (ref "X1") (pin "B6") (pinfunction "B_B6") (pintype "passive"))
    )
    (net (code "52") (name "BRD-ADDR-REG1") (class "Default")
      (node (ref "IC2") (pin "13") (pinfunction "B_13") (pintype "input"))
      (node (ref "IC2") (pin "3") (pinfunction "B_3") (pintype "input"))
      (node (ref "X1") (pin "B5") (pinfunction "B_B5") (pintype "passive"))
    )
    (net (code "53") (name "BRD-IN-ID0") (class "Default")
      (node (ref "IC12") (pin "14") (pinfunction "A_14") (pintype "input"))
      (node (ref "X1") (pin "B18") (pinfunction "B_B18") (pintype "passive"))
    )
    (net (code "54") (name "BRD-IN-ID1") (class "Default")
      (node (ref "IC12") (pin "13") (pinfunction "B_13") (pintype "input"))
      (node (ref "X1") (pin "B19") (pinfunction "B_B19") (pintype "passive"))
    )
    (net (code "55") (name "BRD-OUT-ID0") (class "Default")
      (node (ref "IC11") (pin "14") (pinfunction "A_14") (pintype "input"))
      (node (ref "X1") (pin "B14") (pinfunction "B_B14") (pintype "passive"))
    )
    (net (code "56") (name "BRD-OUT-ID1") (class "Default")
      (node (ref "IC11") (pin "13") (pinfunction "B_13") (pintype "input"))
      (node (ref "X1") (pin "B15") (pinfunction "B_B15") (pintype "passive"))
    )
    (net (code "57") (name "CLK0H") (class "Default")
      (node (ref "IC14") (pin "4") (pinfunction "O_4") (pintype "output"))
      (node (ref "IC16") (pin "11") (pinfunction "CLK_11") (pintype "input"))
      (node (ref "JP5") (pin "23") (pinfunction "23_23") (pintype "passive"))
    )
    (net (code "58") (name "CLK0L") (class "Default")
      (node (ref "IC14") (pin "1") (pinfunction "O_1") (pintype "output"))
      (node (ref "IC15") (pin "11") (pinfunction "CLK_11") (pintype "input"))
      (node (ref "JP5") (pin "25") (pinfunction "25_25") (pintype "passive"))
    )
    (net (code "59") (name "CLK1H") (class "Default")
      (node (ref "IC14") (pin "13") (pinfunction "O_13") (pintype "output"))
      (node (ref "IC18") (pin "11") (pinfunction "CLK_11") (pintype "input"))
      (node (ref "JP5") (pin "19") (pinfunction "19_19") (pintype "passive"))
    )
    (net (code "60") (name "CLK1L") (class "Default")
      (node (ref "IC14") (pin "10") (pinfunction "O_10") (pintype "output"))
      (node (ref "IC17") (pin "11") (pinfunction "CLK_11") (pintype "input"))
      (node (ref "JP5") (pin "21") (pinfunction "21_21") (pintype "passive"))
    )
    (net (code "61") (name "CLK2H") (class "Default")
      (node (ref "IC20") (pin "4") (pinfunction "O_4") (pintype "output"))
      (node (ref "IC22") (pin "11") (pinfunction "CLK_11") (pintype "input"))
      (node (ref "JP5") (pin "24") (pinfunction "24_24") (pintype "passive"))
    )
    (net (code "62") (name "CLK2L") (class "Default")
      (node (ref "IC20") (pin "1") (pinfunction "O_1") (pintype "output"))
      (node (ref "IC21") (pin "11") (pinfunction "CLK_11") (pintype "input"))
      (node (ref "JP5") (pin "26") (pinfunction "26_26") (pintype "passive"))
    )
    (net (code "63") (name "CLK3H") (class "Default")
      (node (ref "IC20") (pin "13") (pinfunction "O_13") (pintype "output"))
      (node (ref "IC24") (pin "11") (pinfunction "CLK_11") (pintype "input"))
      (node (ref "JP5") (pin "20") (pinfunction "20_20") (pintype "passive"))
    )
    (net (code "64") (name "CLK3L") (class "Default")
      (node (ref "IC20") (pin "10") (pinfunction "O_10") (pintype "output"))
      (node (ref "IC23") (pin "11") (pinfunction "CLK_11") (pintype "input"))
      (node (ref "JP5") (pin "22") (pinfunction "22_22") (pintype "passive"))
    )
    (net (code "65") (name "DATA-REG-IN-ID0") (class "Default")
      (node (ref "IC12") (pin "2") (pinfunction "A_2") (pintype "input"))
      (node (ref "X1") (pin "B16") (pinfunction "B_B16") (pintype "passive"))
    )
    (net (code "66") (name "DATA-REG-IN-ID1") (class "Default")
      (node (ref "IC12") (pin "3") (pinfunction "B_3") (pintype "input"))
      (node (ref "X1") (pin "B17") (pinfunction "B_B17") (pintype "passive"))
    )
    (net (code "67") (name "DATA-REG-OUT-ID0") (class "Default")
      (node (ref "IC11") (pin "2") (pinfunction "A_2") (pintype "input"))
      (node (ref "X1") (pin "B12") (pinfunction "B_B12") (pintype "passive"))
    )
    (net (code "68") (name "DATA-REG-OUT-ID1") (class "Default")
      (node (ref "IC11") (pin "3") (pinfunction "B_3") (pintype "input"))
      (node (ref "X1") (pin "B13") (pinfunction "B_B13") (pintype "passive"))
    )
    (net (code "69") (name "DATA-REG-RD-HI") (class "Default")
      (node (ref "IC1") (pin "5") (pinfunction "I_5") (pintype "input"))
      (node (ref "X1") (pin "B22") (pinfunction "B_B22") (pintype "passive"))
    )
    (net (code "70") (name "DATA-REG-RD-LO") (class "Default")
      (node (ref "IC1") (pin "1") (pinfunction "I_1") (pintype "input"))
      (node (ref "X1") (pin "B20") (pinfunction "B_B20") (pintype "passive"))
    )
    (net (code "71") (name "DATA-REG-WR-HI") (class "Default")
      (node (ref "IC1") (pin "9") (pinfunction "I_9") (pintype "input"))
      (node (ref "X1") (pin "B23") (pinfunction "B_B23") (pintype "passive"))
    )
    (net (code "72") (name "DATA-REG-WR-LO") (class "Default")
      (node (ref "IC1") (pin "3") (pinfunction "I_3") (pintype "input"))
      (node (ref "X1") (pin "B21") (pinfunction "B_B21") (pintype "passive"))
    )
    (net (code "73") (name "DATA0") (class "Default")
      (node (ref "IC7") (pin "2") (pinfunction "A1_2") (pintype "bidirectional"))
      (node (ref "IC9") (pin "2") (pinfunction "A1_2") (pintype "bidirectional"))
      (node (ref "X1") (pin "A20") (pinfunction "B_A20") (pintype "passive"))
    )
    (net (code "74") (name "DATA1") (class "Default")
      (node (ref "IC7") (pin "3") (pinfunction "A2_3") (pintype "bidirectional"))
      (node (ref "IC9") (pin "3") (pinfunction "A2_3") (pintype "bidirectional"))
      (node (ref "X1") (pin "A21") (pinfunction "B_A21") (pintype "passive"))
    )
    (net (code "75") (name "DATA2") (class "Default")
      (node (ref "IC7") (pin "4") (pinfunction "A3_4") (pintype "bidirectional"))
      (node (ref "IC9") (pin "4") (pinfunction "A3_4") (pintype "bidirectional"))
      (node (ref "X1") (pin "A22") (pinfunction "B_A22") (pintype "passive"))
    )
    (net (code "76") (name "DATA3") (class "Default")
      (node (ref "IC7") (pin "5") (pinfunction "A4_5") (pintype "bidirectional"))
      (node (ref "IC9") (pin "5") (pinfunction "A4_5") (pintype "bidirectional"))
      (node (ref "X1") (pin "A23") (pinfunction "B_A23") (pintype "passive"))
    )
    (net (code "77") (name "DATA4") (class "Default")
      (node (ref "IC7") (pin "6") (pinfunction "A5_6") (pintype "bidirectional"))
      (node (ref "IC9") (pin "6") (pinfunction "A5_6") (pintype "bidirectional"))
      (node (ref "X1") (pin "A24") (pinfunction "B_A24") (pintype "passive"))
    )
    (net (code "78") (name "DATA5") (class "Default")
      (node (ref "IC7") (pin "7") (pinfunction "A6_7") (pintype "bidirectional"))
      (node (ref "IC9") (pin "7") (pinfunction "A6_7") (pintype "bidirectional"))
      (node (ref "X1") (pin "A25") (pinfunction "B_A25") (pintype "passive"))
    )
    (net (code "79") (name "DATA6") (class "Default")
      (node (ref "IC7") (pin "8") (pinfunction "A7_8") (pintype "bidirectional"))
      (node (ref "IC9") (pin "8") (pinfunction "A7_8") (pintype "bidirectional"))
      (node (ref "X1") (pin "A26") (pinfunction "B_A26") (pintype "passive"))
    )
    (net (code "80") (name "DATA7") (class "Default")
      (node (ref "IC7") (pin "9") (pinfunction "A8_9") (pintype "bidirectional"))
      (node (ref "IC9") (pin "9") (pinfunction "A8_9") (pintype "bidirectional"))
      (node (ref "X1") (pin "A27") (pinfunction "B_A27") (pintype "passive"))
    )
    (net (code "81") (name "DATA8") (class "Default")
      (node (ref "IC8") (pin "2") (pinfunction "A1_2") (pintype "bidirectional"))
      (node (ref "X1") (pin "C23") (pinfunction "B_C23") (pintype "passive"))
    )
    (net (code "82") (name "DATA9") (class "Default")
      (node (ref "IC8") (pin "3") (pinfunction "A2_3") (pintype "bidirectional"))
      (node (ref "X1") (pin "C24") (pinfunction "B_C24") (pintype "passive"))
    )
    (net (code "83") (name "DATA10") (class "Default")
      (node (ref "IC8") (pin "4") (pinfunction "A3_4") (pintype "bidirectional"))
      (node (ref "X1") (pin "C25") (pinfunction "B_C25") (pintype "passive"))
    )
    (net (code "84") (name "DATA11") (class "Default")
      (node (ref "IC8") (pin "5") (pinfunction "A4_5") (pintype "bidirectional"))
      (node (ref "X1") (pin "C26") (pinfunction "B_C26") (pintype "passive"))
    )
    (net (code "85") (name "DATA12") (class "Default")
      (node (ref "IC8") (pin "6") (pinfunction "A5_6") (pintype "bidirectional"))
      (node (ref "X1") (pin "C27") (pinfunction "B_C27") (pintype "passive"))
    )
    (net (code "86") (name "DATA13") (class "Default")
      (node (ref "IC8") (pin "7") (pinfunction "A6_7") (pintype "bidirectional"))
      (node (ref "X1") (pin "C28") (pinfunction "B_C28") (pintype "passive"))
    )
    (net (code "87") (name "DATA14") (class "Default")
      (node (ref "IC8") (pin "8") (pinfunction "A7_8") (pintype "bidirectional"))
      (node (ref "X1") (pin "C29") (pinfunction "B_C29") (pintype "passive"))
    )
    (net (code "88") (name "DATA15") (class "Default")
      (node (ref "IC8") (pin "9") (pinfunction "A8_9") (pintype "bidirectional"))
      (node (ref "X1") (pin "C30") (pinfunction "B_C30") (pintype "passive"))
    )
    (net (code "89") (name "DIR") (class "Default")
      (node (ref "IC6") (pin "8") (pinfunction "O_8") (pintype "output"))
      (node (ref "IC7") (pin "1") (pinfunction "DIR_1") (pintype "input"))
      (node (ref "IC8") (pin "1") (pinfunction "DIR_1") (pintype "input"))
      (node (ref "IC9") (pin "1") (pinfunction "DIR_1") (pintype "input"))
    )
    (net (code "90") (name "GND") (class "Default")
      (node (ref "C1") (pin "2") (pinfunction "2_2") (pintype "passive"))
      (node (ref "C10") (pin "2") (pinfunction "2_2") (pintype "passive"))
      (node (ref "C12") (pin "2") (pinfunction "2_2") (pintype "passive"))
      (node (ref "C13") (pin "2") (pinfunction "2_2") (pintype "passive"))
      (node (ref "C14") (pin "2") (pinfunction "2_2") (pintype "passive"))
      (node (ref "C15") (pin "2") (pinfunction "2_2") (pintype "passive"))
      (node (ref "C16") (pin "2") (pinfunction "2_2") (pintype "passive"))
      (node (ref "C17") (pin "2") (pinfunction "2_2") (pintype "passive"))
      (node (ref "C18") (pin "2") (pinfunction "2_2") (pintype "passive"))
      (node (ref "C19") (pin "2") (pinfunction "2_2") (pintype "passive"))
      (node (ref "C2") (pin "2") (pinfunction "2_2") (pintype "passive"))
      (node (ref "C20") (pin "2") (pinfunction "2_2") (pintype "passive"))
      (node (ref "C21") (pin "2") (pinfunction "2_2") (pintype "passive"))
      (node (ref "C22") (pin "2") (pinfunction "2_2") (pintype "passive"))
      (node (ref "C23") (pin "2") (pinfunction "2_2") (pintype "passive"))
      (node (ref "C24") (pin "2") (pinfunction "2_2") (pintype "passive"))
      (node (ref "C3") (pin "2") (pinfunction "2_2") (pintype "passive"))
      (node (ref "C4") (pin "2") (pinfunction "2_2") (pintype "passive"))
      (node (ref "C5") (pin "2") (pinfunction "2_2") (pintype "passive"))
      (node (ref "C6") (pin "2") (pinfunction "2_2") (pintype "passive"))
      (node (ref "C7") (pin "2") (pinfunction "2_2") (pintype "passive"))
      (node (ref "C8") (pin "2") (pinfunction "2_2") (pintype "passive"))
      (node (ref "C9") (pin "2") (pinfunction "2_2") (pintype "passive"))
      (node (ref "JP5") (pin "1") (pinfunction "1_1") (pintype "passive"))
      (node (ref "JP5") (pin "2") (pinfunction "2_2") (pintype "passive"))
      (node (ref "JP5") (pin "27") (pinfunction "27_27") (pintype "passive"))
      (node (ref "JP5") (pin "28") (pinfunction "28_28") (pintype "passive"))
      (node (ref "PWR") (pin "K") (pinfunction "C_K") (pintype "passive"))
      (node (ref "X1") (pin "A1") (pinfunction "B_A1") (pintype "passive"))
      (node (ref "X1") (pin "A32") (pinfunction "B_A32") (pintype "passive"))
      (node (ref "X1") (pin "B1") (pinfunction "B_B1") (pintype "passive"))
      (node (ref "X1") (pin "B32") (pinfunction "B_B32") (pintype "passive"))
      (node (ref "X1") (pin "C1") (pinfunction "B_C1") (pintype "passive"))
      (node (ref "X1") (pin "C32") (pinfunction "B_C32") (pintype "passive"))
    )
    (net (code "91") (name "H{slash}L-SWAP") (class "Default")
      (node (ref "IC5") (pin "13") (pinfunction "I1_13") (pintype "input"))
      (node (ref "IC6") (pin "1") (pinfunction "I0_1") (pintype "input"))
      (node (ref "IC6") (pin "2") (pinfunction "I1_2") (pintype "input"))
      (node (ref "X1") (pin "A30") (pinfunction "B_A30") (pintype "passive"))
    )
    (net (code "92") (name "Net-(IC1E-O)") (class "Default")
      (node (ref "IC1") (pin "10") (pinfunction "O_10") (pintype "output"))
      (node (ref "IC2") (pin "1") (pinfunction "G_1") (pintype "input"))
    )
    (net (code "93") (name "Net-(IC1F-I)") (class "Default")
      (node (ref "IC1") (pin "13") (pinfunction "I_13") (pintype "input"))
      (node (ref "JP1") (pin "2") (pinfunction "2_2") (pintype "passive"))
      (node (ref "JP1") (pin "4") (pinfunction "4_4") (pintype "passive"))
      (node (ref "JP1") (pin "6") (pinfunction "6_6") (pintype "passive"))
      (node (ref "JP1") (pin "8") (pinfunction "8_8") (pintype "passive"))
    )
    (net (code "94") (name "Net-(IC1F-O)") (class "Default")
      (node (ref "IC1") (pin "12") (pinfunction "O_12") (pintype "output"))
      (node (ref "IC3") (pin "11") (pinfunction "CLK_11") (pintype "input"))
      (node (ref "IC4") (pin "11") (pinfunction "CLK_11") (pintype "input"))
    )
    (net (code "95") (name "Net-(IC2A-Y0)") (class "Default")
      (node (ref "IC2") (pin "4") (pinfunction "Y0_4") (pintype "output"))
      (node (ref "JP1") (pin "1") (pinfunction "1_1") (pintype "passive"))
    )
    (net (code "96") (name "Net-(IC2A-Y1)") (class "Default")
      (node (ref "IC2") (pin "5") (pinfunction "Y1_5") (pintype "output"))
      (node (ref "JP1") (pin "3") (pinfunction "3_3") (pintype "passive"))
    )
    (net (code "97") (name "Net-(IC2A-Y2)") (class "Default")
      (node (ref "IC2") (pin "6") (pinfunction "Y2_6") (pintype "output"))
      (node (ref "JP1") (pin "5") (pinfunction "5_5") (pintype "passive"))
    )
    (net (code "98") (name "Net-(IC2A-Y3)") (class "Default")
      (node (ref "IC2") (pin "7") (pinfunction "Y3_7") (pintype "output"))
      (node (ref "JP1") (pin "7") (pinfunction "7_7") (pintype "passive"))
    )
    (net (code "99") (name "Net-(IC2B-G)") (class "Default")
      (node (ref "IC2") (pin "15") (pinfunction "G_15") (pintype "input"))
      (node (ref "IC6") (pin "6") (pinfunction "O_6") (pintype "output"))
    )
    (net (code "100") (name "Net-(IC2B-Y0)") (class "Default")
      (node (ref "IC2") (pin "12") (pinfunction "Y0_12") (pintype "output"))
      (node (ref "JP2") (pin "1") (pinfunction "1_1") (pintype "passive"))
    )
    (net (code "101") (name "Net-(IC2B-Y1)") (class "Default")
      (node (ref "IC2") (pin "11") (pinfunction "Y1_11") (pintype "output"))
      (node (ref "JP2") (pin "3") (pinfunction "3_3") (pintype "passive"))
    )
    (net (code "102") (name "Net-(IC2B-Y2)") (class "Default")
      (node (ref "IC2") (pin "10") (pinfunction "Y2_10") (pintype "output"))
      (node (ref "JP2") (pin "5") (pinfunction "5_5") (pintype "passive"))
    )
    (net (code "103") (name "Net-(IC2B-Y3)") (class "Default")
      (node (ref "IC2") (pin "9") (pinfunction "Y3_9") (pintype "output"))
      (node (ref "JP2") (pin "7") (pinfunction "7_7") (pintype "passive"))
    )
    (net (code "104") (name "Net-(IC3A-OC)") (class "Default")
      (node (ref "IC3") (pin "1") (pinfunction "OC_1") (pintype "input"))
      (node (ref "IC4") (pin "1") (pinfunction "OC_1") (pintype "input"))
      (node (ref "JP2") (pin "2") (pinfunction "2_2") (pintype "passive"))
      (node (ref "JP2") (pin "4") (pinfunction "4_4") (pintype "passive"))
      (node (ref "JP2") (pin "6") (pinfunction "6_6") (pintype "passive"))
      (node (ref "JP2") (pin "8") (pinfunction "8_8") (pintype "passive"))
    )
    (net (code "105") (name "Net-(IC5A-O)") (class "Default")
      (node (ref "IC5") (pin "10") (pinfunction "I1_10") (pintype "input"))
      (node (ref "IC5") (pin "12") (pinfunction "I0_12") (pintype "input"))
      (node (ref "IC5") (pin "3") (pinfunction "O_3") (pintype "output"))
      (node (ref "IC5") (pin "4") (pinfunction "I0_4") (pintype "input"))
      (node (ref "IC5") (pin "5") (pinfunction "I1_5") (pintype "input"))
    )
    (net (code "106") (name "Net-(IC5B-O)") (class "Default")
      (node (ref "IC5") (pin "6") (pinfunction "O_6") (pintype "output"))
      (node (ref "IC8") (pin "19") (pinfunction "G_19") (pintype "input"))
    )
    (net (code "107") (name "Net-(IC5C-I0)") (class "Default")
      (node (ref "IC5") (pin "9") (pinfunction "I0_9") (pintype "input"))
      (node (ref "IC6") (pin "3") (pinfunction "O_3") (pintype "output"))
    )
    (net (code "108") (name "Net-(IC5C-O)") (class "Default")
      (node (ref "IC5") (pin "8") (pinfunction "O_8") (pintype "output"))
      (node (ref "IC7") (pin "19") (pinfunction "G_19") (pintype "input"))
    )
    (net (code "109") (name "Net-(IC5D-O)") (class "Default")
      (node (ref "IC5") (pin "11") (pinfunction "O_11") (pintype "output"))
      (node (ref "IC9") (pin "19") (pinfunction "G_19") (pintype "input"))
    )
    (net (code "110") (name "Net-(IC11B-Y0)") (class "Default")
      (node (ref "IC11") (pin "12") (pinfunction "Y0_12") (pintype "output"))
      (node (ref "JP3") (pin "1") (pinfunction "1_1") (pintype "passive"))
    )
    (net (code "111") (name "Net-(IC11B-Y1)") (class "Default")
      (node (ref "IC11") (pin "11") (pinfunction "Y1_11") (pintype "output"))
      (node (ref "JP3") (pin "3") (pinfunction "3_3") (pintype "passive"))
    )
    (net (code "112") (name "Net-(IC11B-Y2)") (class "Default")
      (node (ref "IC11") (pin "10") (pinfunction "Y2_10") (pintype "output"))
      (node (ref "JP3") (pin "5") (pinfunction "5_5") (pintype "passive"))
    )
    (net (code "113") (name "Net-(IC11B-Y3)") (class "Default")
      (node (ref "IC11") (pin "9") (pinfunction "Y3_9") (pintype "output"))
      (node (ref "JP3") (pin "7") (pinfunction "7_7") (pintype "passive"))
    )
    (net (code "114") (name "Net-(IC12B-Y0)") (class "Default")
      (node (ref "IC12") (pin "12") (pinfunction "Y0_12") (pintype "output"))
      (node (ref "JP4") (pin "1") (pinfunction "1_1") (pintype "passive"))
    )
    (net (code "115") (name "Net-(IC12B-Y1)") (class "Default")
      (node (ref "IC12") (pin "11") (pinfunction "Y1_11") (pintype "output"))
      (node (ref "JP4") (pin "3") (pinfunction "3_3") (pintype "passive"))
    )
    (net (code "116") (name "Net-(IC12B-Y2)") (class "Default")
      (node (ref "IC12") (pin "10") (pinfunction "Y2_10") (pintype "output"))
      (node (ref "JP4") (pin "5") (pinfunction "5_5") (pintype "passive"))
    )
    (net (code "117") (name "Net-(IC12B-Y3)") (class "Default")
      (node (ref "IC12") (pin "9") (pinfunction "Y3_9") (pintype "output"))
      (node (ref "JP4") (pin "7") (pinfunction "7_7") (pintype "passive"))
    )
    (net (code "118") (name "Net-(IC13A-O)") (class "Default")
      (node (ref "IC13") (pin "3") (pinfunction "O_3") (pintype "output"))
      (node (ref "IC15") (pin "1") (pinfunction "OC_1") (pintype "input"))
    )
    (net (code "119") (name "Net-(IC13B-O)") (class "Default")
      (node (ref "IC13") (pin "6") (pinfunction "O_6") (pintype "output"))
      (node (ref "IC16") (pin "1") (pinfunction "OC_1") (pintype "input"))
    )
    (net (code "120") (name "Net-(IC13C-O)") (class "Default")
      (node (ref "IC13") (pin "8") (pinfunction "O_8") (pintype "output"))
      (node (ref "IC17") (pin "1") (pinfunction "OC_1") (pintype "input"))
    )
    (net (code "121") (name "Net-(IC13D-O)") (class "Default")
      (node (ref "IC13") (pin "11") (pinfunction "O_11") (pintype "output"))
      (node (ref "IC18") (pin "1") (pinfunction "OC_1") (pintype "input"))
    )
    (net (code "122") (name "Net-(IC19A-O)") (class "Default")
      (node (ref "IC19") (pin "3") (pinfunction "O_3") (pintype "output"))
      (node (ref "IC21") (pin "1") (pinfunction "OC_1") (pintype "input"))
    )
    (net (code "123") (name "Net-(IC19B-O)") (class "Default")
      (node (ref "IC19") (pin "6") (pinfunction "O_6") (pintype "output"))
      (node (ref "IC22") (pin "1") (pinfunction "OC_1") (pintype "input"))
    )
    (net (code "124") (name "Net-(IC19C-O)") (class "Default")
      (node (ref "IC19") (pin "8") (pinfunction "O_8") (pintype "output"))
      (node (ref "IC23") (pin "1") (pinfunction "OC_1") (pintype "input"))
    )
    (net (code "125") (name "Net-(IC19D-O)") (class "Default")
      (node (ref "IC19") (pin "11") (pinfunction "O_11") (pintype "output"))
      (node (ref "IC24") (pin "1") (pinfunction "OC_1") (pintype "input"))
    )
    (net (code "126") (name "Net-(PWR-PadA)") (class "Default")
      (node (ref "PWR") (pin "A") (pinfunction "A_A") (pintype "passive"))
      (node (ref "R1") (pin "1") (pinfunction "1_1") (pintype "passive"))
    )
    (net (code "127") (name "REG-FUNC") (class "Default")
      (node (ref "IC6") (pin "12") (pinfunction "I0_12") (pintype "input"))
      (node (ref "IC6") (pin "13") (pinfunction "I1_13") (pintype "input"))
      (node (ref "X1") (pin "B7") (pinfunction "B_B7") (pintype "passive"))
    )
    (net (code "128") (name "VCC") (class "Default")
      (node (ref "C1") (pin "1") (pinfunction "1_1") (pintype "passive"))
      (node (ref "C10") (pin "1") (pinfunction "1_1") (pintype "passive"))
      (node (ref "C12") (pin "1") (pinfunction "1_1") (pintype "passive"))
      (node (ref "C13") (pin "1") (pinfunction "1_1") (pintype "passive"))
      (node (ref "C14") (pin "1") (pinfunction "1_1") (pintype "passive"))
      (node (ref "C15") (pin "1") (pinfunction "1_1") (pintype "passive"))
      (node (ref "C16") (pin "1") (pinfunction "1_1") (pintype "passive"))
      (node (ref "C17") (pin "1") (pinfunction "1_1") (pintype "passive"))
      (node (ref "C18") (pin "1") (pinfunction "1_1") (pintype "passive"))
      (node (ref "C19") (pin "1") (pinfunction "1_1") (pintype "passive"))
      (node (ref "C2") (pin "1") (pinfunction "1_1") (pintype "passive"))
      (node (ref "C20") (pin "1") (pinfunction "1_1") (pintype "passive"))
      (node (ref "C21") (pin "1") (pinfunction "1_1") (pintype "passive"))
      (node (ref "C22") (pin "1") (pinfunction "1_1") (pintype "passive"))
      (node (ref "C23") (pin "1") (pinfunction "1_1") (pintype "passive"))
      (node (ref "C24") (pin "1") (pinfunction "1_1") (pintype "passive"))
      (node (ref "C3") (pin "1") (pinfunction "1_1") (pintype "passive"))
      (node (ref "C4") (pin "1") (pinfunction "1_1") (pintype "passive"))
      (node (ref "C5") (pin "1") (pinfunction "1_1") (pintype "passive"))
      (node (ref "C6") (pin "1") (pinfunction "1_1") (pintype "passive"))
      (node (ref "C7") (pin "1") (pinfunction "1_1") (pintype "passive"))
      (node (ref "C8") (pin "1") (pinfunction "1_1") (pintype "passive"))
      (node (ref "C9") (pin "1") (pinfunction "1_1") (pintype "passive"))
      (node (ref "R1") (pin "2") (pinfunction "2_2") (pintype "passive"))
      (node (ref "RN1") (pin "1") (pinfunction "1_1") (pintype "passive"))
      (node (ref "RN2") (pin "1") (pinfunction "1_1") (pintype "passive"))
      (node (ref "X1") (pin "A2") (pinfunction "B_A2") (pintype "passive"))
      (node (ref "X1") (pin "A31") (pinfunction "B_A31") (pintype "passive"))
      (node (ref "X1") (pin "B2") (pinfunction "B_B2") (pintype "passive"))
      (node (ref "X1") (pin "B31") (pinfunction "B_B31") (pintype "passive"))
      (node (ref "X1") (pin "C2") (pinfunction "B_C2") (pintype "passive"))
      (node (ref "X1") (pin "C31") (pinfunction "B_C31") (pintype "passive"))
    )
    (net (code "129") (name "unconnected-(X1AH-B-PadB10)") (class "Default")
      (node (ref "X1") (pin "B10") (pinfunction "B_B10") (pintype "passive"))
    )
    (net (code "130") (name "unconnected-(X1AI-B-PadB11)") (class "Default")
      (node (ref "X1") (pin "B11") (pinfunction "B_B11") (pintype "passive"))
    )
    (net (code "131") (name "unconnected-(X1AW-B-PadB24)") (class "Default")
      (node (ref "X1") (pin "B24") (pinfunction "B_B24") (pintype "passive"))
    )
    (net (code "132") (name "unconnected-(X1AX-B-PadB25)") (class "Default")
      (node (ref "X1") (pin "B25") (pinfunction "B_B25") (pintype "passive"))
    )
    (net (code "133") (name "unconnected-(X1AY-B-PadB26)") (class "Default")
      (node (ref "X1") (pin "B26") (pinfunction "B_B26") (pintype "passive"))
    )
    (net (code "134") (name "unconnected-(X1AZ-B-PadB27)") (class "Default")
      (node (ref "X1") (pin "B27") (pinfunction "B_B27") (pintype "passive"))
    )
    (net (code "135") (name "unconnected-(X1BA-B-PadB28)") (class "Default")
      (node (ref "X1") (pin "B28") (pinfunction "B_B28") (pintype "passive"))
    )
    (net (code "136") (name "unconnected-(X1BB-B-PadB29)") (class "Default")
      (node (ref "X1") (pin "B29") (pinfunction "B_B29") (pintype "passive"))
    )
    (net (code "137") (name "unconnected-(X1BD-B-PadB30)") (class "Default")
      (node (ref "X1") (pin "B30") (pinfunction "B_B30") (pintype "passive"))
    )
    (net (code "138") (name "unconnected-(X1BL-B-PadB9)") (class "Default")
      (node (ref "X1") (pin "B9") (pinfunction "B_B9") (pintype "passive"))
    )
    (net (code "139") (name "unconnected-(X1BN-B-PadC10)") (class "Default")
      (node (ref "X1") (pin "C10") (pinfunction "B_C10") (pintype "passive"))
    )
    (net (code "140") (name "unconnected-(X1BO-B-PadC11)") (class "Default")
      (node (ref "X1") (pin "C11") (pinfunction "B_C11") (pintype "passive"))
    )
    (net (code "141") (name "unconnected-(X1BP-B-PadC12)") (class "Default")
      (node (ref "X1") (pin "C12") (pinfunction "B_C12") (pintype "passive"))
    )
    (net (code "142") (name "unconnected-(X1BQ-B-PadC13)") (class "Default")
      (node (ref "X1") (pin "C13") (pinfunction "B_C13") (pintype "passive"))
    )
    (net (code "143") (name "unconnected-(X1BR-B-PadC14)") (class "Default")
      (node (ref "X1") (pin "C14") (pinfunction "B_C14") (pintype "passive"))
    )
    (net (code "144") (name "unconnected-(X1BS-B-PadC15)") (class "Default")
      (node (ref "X1") (pin "C15") (pinfunction "B_C15") (pintype "passive"))
    )
    (net (code "145") (name "unconnected-(X1BT-B-PadC16)") (class "Default")
      (node (ref "X1") (pin "C16") (pinfunction "B_C16") (pintype "passive"))
    )
    (net (code "146") (name "unconnected-(X1BU-B-PadC17)") (class "Default")
      (node (ref "X1") (pin "C17") (pinfunction "B_C17") (pintype "passive"))
    )
    (net (code "147") (name "unconnected-(X1BV-B-PadC18)") (class "Default")
      (node (ref "X1") (pin "C18") (pinfunction "B_C18") (pintype "passive"))
    )
    (net (code "148") (name "unconnected-(X1BW-B-PadC19)") (class "Default")
      (node (ref "X1") (pin "C19") (pinfunction "B_C19") (pintype "passive"))
    )
    (net (code "149") (name "unconnected-(X1BY-B-PadC20)") (class "Default")
      (node (ref "X1") (pin "C20") (pinfunction "B_C20") (pintype "passive"))
    )
    (net (code "150") (name "unconnected-(X1BZ-B-PadC21)") (class "Default")
      (node (ref "X1") (pin "C21") (pinfunction "B_C21") (pintype "passive"))
    )
    (net (code "151") (name "unconnected-(X1CA-B-PadC22)") (class "Default")
      (node (ref "X1") (pin "C22") (pinfunction "B_C22") (pintype "passive"))
    )
    (net (code "152") (name "unconnected-(X1CM-B-PadC4)") (class "Default")
      (node (ref "X1") (pin "C4") (pinfunction "B_C4") (pintype "passive"))
    )
    (net (code "153") (name "unconnected-(X1CN-B-PadC5)") (class "Default")
      (node (ref "X1") (pin "C5") (pinfunction "B_C5") (pintype "passive"))
    )
    (net (code "154") (name "unconnected-(X1CO-B-PadC6)") (class "Default")
      (node (ref "X1") (pin "C6") (pinfunction "B_C6") (pintype "passive"))
    )
    (net (code "155") (name "unconnected-(X1CP-B-PadC7)") (class "Default")
      (node (ref "X1") (pin "C7") (pinfunction "B_C7") (pintype "passive"))
    )
    (net (code "156") (name "unconnected-(X1CQ-B-PadC8)") (class "Default")
      (node (ref "X1") (pin "C8") (pinfunction "B_C8") (pintype "passive"))
    )
    (net (code "157") (name "unconnected-(X1CR-B-PadC9)") (class "Default")
      (node (ref "X1") (pin "C9") (pinfunction "B_C9") (pintype "passive"))
    )
    (net (code "158") (name "unconnected-(X1U-B-PadA28)") (class "Default")
      (node (ref "X1") (pin "A28") (pinfunction "B_A28") (pintype "passive"))
    )
    (net (code "159") (name "unconnected-(X1V-B-PadA29)") (class "Default")
      (node (ref "X1") (pin "A29") (pinfunction "B_A29") (pintype "passive"))
    )
  )
)
